# system.net
KiCad netlist of a schematic drawn in Altium Designer
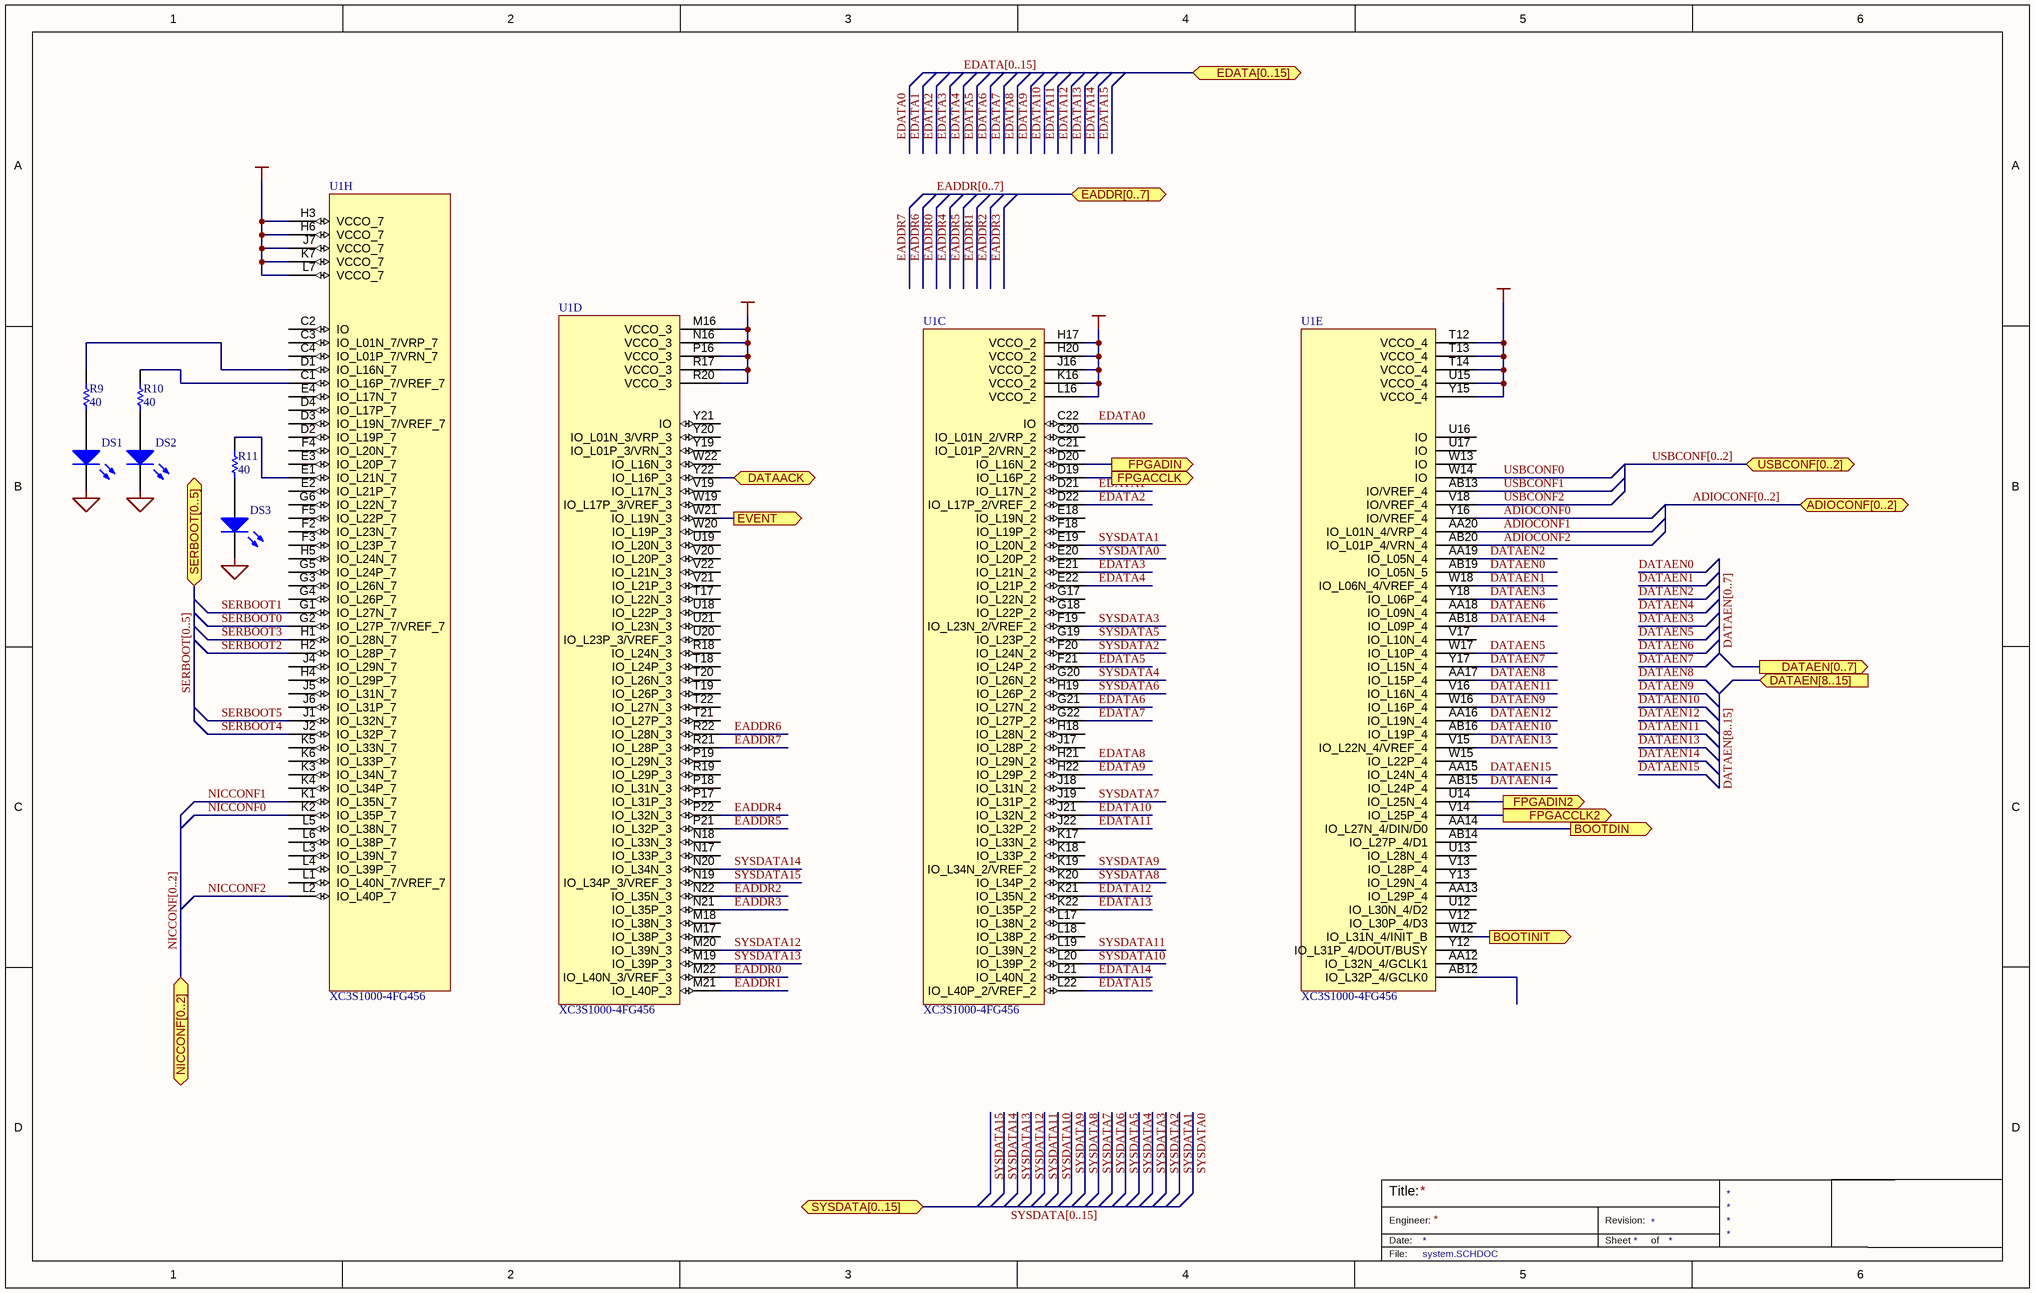
[diagram p0: system.SCHDOC]

(export (version "E")
  (design (tool "Eeschema 10.0.6"))
  (components
    (comp (ref "DS1")
      (value "LED0")
      (footprint "T-1_LED")
      (description "Typical INFRARED GaAs LED")
      (fields (field (name "MANUFACTURER") "Generic Components") (field (name "PUBLISHER") "Altium Limited"))
      (libsource (lib "Miscellaneous Devices") (part "LED0"))
    )
    (comp (ref "DS2")
      (value "LED0")
      (footprint "T-1_LED")
      (description "Typical INFRARED GaAs LED")
      (fields (field (name "MANUFACTURER") "Generic Components") (field (name "PUBLISHER") "Altium Limited"))
      (libsource (lib "Miscellaneous Devices") (part "LED0"))
    )
    (comp (ref "DS3")
      (value "LED0")
      (footprint "T-1_LED")
      (description "Typical INFRARED GaAs LED")
      (fields (field (name "MANUFACTURER") "Generic Components") (field (name "PUBLISHER") "Altium Limited"))
      (libsource (lib "Miscellaneous Devices") (part "LED0"))
    )
    (comp (ref "R9")
      (value "40")
      (footprint "CC1608-0603")
      (description "Resistor")
      (fields
        (field (name "MANUFACTURER") "Generic Components")
        (field (name "Comment") "Res1")
        (field (name "PUBLISHER") "Altium Limited")
      )
      (libsource (lib "Miscellaneous Devices") (part "Res1"))
    )
    (comp (ref "R10")
      (value "40")
      (footprint "CC1608-0603")
      (description "Resistor")
      (fields
        (field (name "MANUFACTURER") "Generic Components")
        (field (name "Comment") "Res1")
        (field (name "PUBLISHER") "Altium Limited")
      )
      (libsource (lib "Miscellaneous Devices") (part "Res1"))
    )
    (comp (ref "R11")
      (value "40")
      (footprint "CC1608-0603")
      (description "Resistor")
      (fields
        (field (name "MANUFACTURER") "Generic Components")
        (field (name "Comment") "Res1")
        (field (name "PUBLISHER") "Altium Limited")
      )
      (libsource (lib "Miscellaneous Devices") (part "Res1"))
    )
    (comp (ref "U1")
      (value "XC3S1000-4FG456")
      (footprint "FG456")
      (description "Xilinx Spartan-3 FPGA")
      (libsource (lib "parts") (part "XC3S1000-4FG456"))
    )
  )
  (nets
    (net (code "1") (name "/ADIOCONF0") (class "Default")
      (node (ref "U1") (pin "Y16") (pinfunction "IO/VREF_4_Y16") (pintype "power_in"))
    )
    (net (code "2") (name "/ADIOCONF1") (class "Default")
      (node (ref "U1") (pin "AA20") (pinfunction "IO_L01N_4/VRP_4_AA20") (pintype "power_in"))
    )
    (net (code "3") (name "/ADIOCONF2") (class "Default")
      (node (ref "U1") (pin "AB20") (pinfunction "IO_L01P_4/VRN_4_AB20") (pintype "power_in"))
    )
    (net (code "5") (name "/BOOTDIN") (class "Default")
      (node (ref "U1") (pin "AA14") (pinfunction "IO_L27N_4/DIN/D0_AA14") (pintype "power_in"))
    )
    (net (code "6") (name "/BOOTINIT") (class "Default")
      (node (ref "U1") (pin "W12") (pinfunction "IO_L31N_4/INIT_B_W12") (pintype "power_in"))
    )
    (net (code "7") (name "/DATAACK") (class "Default")
      (node (ref "U1") (pin "Y22") (pinfunction "IO_L16P_3_Y22") (pintype "bidirectional"))
    )
    (net (code "8") (name "/DATAEN0") (class "Default")
      (node (ref "U1") (pin "AB19") (pinfunction "IO_L05N_5_AB19") (pintype "power_in"))
    )
    (net (code "9") (name "/DATAEN1") (class "Default")
      (node (ref "U1") (pin "W18") (pinfunction "IO_L06N_4/VREF_4_W18") (pintype "power_in"))
    )
    (net (code "10") (name "/DATAEN2") (class "Default")
      (node (ref "U1") (pin "AA19") (pinfunction "IO_L05N_4_AA19") (pintype "power_in"))
    )
    (net (code "11") (name "/DATAEN3") (class "Default")
      (node (ref "U1") (pin "Y18") (pinfunction "IO_L06P_4_Y18") (pintype "power_in"))
    )
    (net (code "12") (name "/DATAEN4") (class "Default")
      (node (ref "U1") (pin "AB18") (pinfunction "IO_L09P_4_AB18") (pintype "power_in"))
    )
    (net (code "13") (name "/DATAEN5") (class "Default")
      (node (ref "U1") (pin "W17") (pinfunction "IO_L10P_4_W17") (pintype "power_in"))
    )
    (net (code "14") (name "/DATAEN6") (class "Default")
      (node (ref "U1") (pin "AA18") (pinfunction "IO_L09N_4_AA18") (pintype "power_in"))
    )
    (net (code "15") (name "/DATAEN7") (class "Default")
      (node (ref "U1") (pin "Y17") (pinfunction "IO_L15N_4_Y17") (pintype "power_in"))
    )
    (net (code "16") (name "/DATAEN8") (class "Default")
      (node (ref "U1") (pin "AA17") (pinfunction "IO_L15P_4_AA17") (pintype "power_in"))
    )
    (net (code "17") (name "/DATAEN9") (class "Default")
      (node (ref "U1") (pin "W16") (pinfunction "IO_L16P_4_W16") (pintype "power_in"))
    )
    (net (code "18") (name "/DATAEN10") (class "Default")
      (node (ref "U1") (pin "AB16") (pinfunction "IO_L19P_4_AB16") (pintype "power_in"))
    )
    (net (code "19") (name "/DATAEN11") (class "Default")
      (node (ref "U1") (pin "V16") (pinfunction "IO_L16N_4_V16") (pintype "power_in"))
    )
    (net (code "20") (name "/DATAEN12") (class "Default")
      (node (ref "U1") (pin "AA16") (pinfunction "IO_L19N_4_AA16") (pintype "power_in"))
    )
    (net (code "21") (name "/DATAEN13") (class "Default")
      (node (ref "U1") (pin "V15") (pinfunction "IO_L22N_4/VREF_4_V15") (pintype "power_in"))
    )
    (net (code "22") (name "/DATAEN14") (class "Default")
      (node (ref "U1") (pin "AB15") (pinfunction "IO_L24P_4_AB15") (pintype "power_in"))
    )
    (net (code "23") (name "/DATAEN15") (class "Default")
      (node (ref "U1") (pin "AA15") (pinfunction "IO_L24N_4_AA15") (pintype "power_in"))
    )
    (net (code "26") (name "/EADDR0") (class "Default")
      (node (ref "U1") (pin "M22") (pinfunction "IO_L40N_3/VREF_3_M22") (pintype "bidirectional"))
    )
    (net (code "27") (name "/EADDR1") (class "Default")
      (node (ref "U1") (pin "M21") (pinfunction "IO_L40P_3_M21") (pintype "bidirectional"))
    )
    (net (code "28") (name "/EADDR2") (class "Default")
      (node (ref "U1") (pin "N22") (pinfunction "IO_L35N_3_N22") (pintype "bidirectional"))
    )
    (net (code "29") (name "/EADDR3") (class "Default")
      (node (ref "U1") (pin "N21") (pinfunction "IO_L35P_3_N21") (pintype "bidirectional"))
    )
    (net (code "30") (name "/EADDR4") (class "Default")
      (node (ref "U1") (pin "P22") (pinfunction "IO_L32N_3_P22") (pintype "bidirectional"))
    )
    (net (code "31") (name "/EADDR5") (class "Default")
      (node (ref "U1") (pin "P21") (pinfunction "IO_L32P_3_P21") (pintype "bidirectional"))
    )
    (net (code "32") (name "/EADDR6") (class "Default")
      (node (ref "U1") (pin "R22") (pinfunction "IO_L28N_3_R22") (pintype "bidirectional"))
    )
    (net (code "33") (name "/EADDR7") (class "Default")
      (node (ref "U1") (pin "R21") (pinfunction "IO_L28P_3_R21") (pintype "bidirectional"))
    )
    (net (code "35") (name "/EDATA0") (class "Default")
      (node (ref "U1") (pin "C22") (pinfunction "IO_C22") (pintype "bidirectional"))
    )
    (net (code "36") (name "/EDATA1") (class "Default")
      (node (ref "U1") (pin "D21") (pinfunction "IO_L17N_2_D21") (pintype "bidirectional"))
    )
    (net (code "37") (name "/EDATA2") (class "Default")
      (node (ref "U1") (pin "D22") (pinfunction "IO_L17P_2/VREF_2_D22") (pintype "bidirectional"))
    )
    (net (code "38") (name "/EDATA3") (class "Default")
      (node (ref "U1") (pin "E21") (pinfunction "IO_L21N_2_E21") (pintype "bidirectional"))
    )
    (net (code "39") (name "/EDATA4") (class "Default")
      (node (ref "U1") (pin "E22") (pinfunction "IO_L21P_2_E22") (pintype "bidirectional"))
    )
    (net (code "40") (name "/EDATA5") (class "Default")
      (node (ref "U1") (pin "F21") (pinfunction "IO_L24P_2_F21") (pintype "bidirectional"))
    )
    (net (code "41") (name "/EDATA6") (class "Default")
      (node (ref "U1") (pin "G21") (pinfunction "IO_L27N_2_G21") (pintype "bidirectional"))
    )
    (net (code "42") (name "/EDATA7") (class "Default")
      (node (ref "U1") (pin "G22") (pinfunction "IO_L27P_2_G22") (pintype "bidirectional"))
    )
    (net (code "43") (name "/EDATA8") (class "Default")
      (node (ref "U1") (pin "H21") (pinfunction "IO_L29N_2_H21") (pintype "bidirectional"))
    )
    (net (code "44") (name "/EDATA9") (class "Default")
      (node (ref "U1") (pin "H22") (pinfunction "IO_L29P_2_H22") (pintype "bidirectional"))
    )
    (net (code "45") (name "/EDATA10") (class "Default")
      (node (ref "U1") (pin "J21") (pinfunction "IO_L32N_2_J21") (pintype "bidirectional"))
    )
    (net (code "46") (name "/EDATA11") (class "Default")
      (node (ref "U1") (pin "J22") (pinfunction "IO_L32P_2_J22") (pintype "bidirectional"))
    )
    (net (code "47") (name "/EDATA12") (class "Default")
      (node (ref "U1") (pin "K21") (pinfunction "IO_L35N_2_K21") (pintype "bidirectional"))
    )
    (net (code "48") (name "/EDATA13") (class "Default")
      (node (ref "U1") (pin "K22") (pinfunction "IO_L35P_2_K22") (pintype "bidirectional"))
    )
    (net (code "49") (name "/EDATA14") (class "Default")
      (node (ref "U1") (pin "L21") (pinfunction "IO_L40N_2_L21") (pintype "bidirectional"))
    )
    (net (code "50") (name "/EDATA15") (class "Default")
      (node (ref "U1") (pin "L22") (pinfunction "IO_L40P_2/VREF_2_L22") (pintype "bidirectional"))
    )
    (net (code "52") (name "/EVENT") (class "Default")
      (node (ref "U1") (pin "W21") (pinfunction "IO_L19N_3_W21") (pintype "bidirectional"))
    )
    (net (code "53") (name "/FPGACCLK") (class "Default")
      (node (ref "U1") (pin "D19") (pinfunction "IO_L16P_2_D19") (pintype "bidirectional"))
    )
    (net (code "54") (name "/FPGACCLK2") (class "Default")
      (node (ref "U1") (pin "V14") (pinfunction "IO_L25P_4_V14") (pintype "power_in"))
    )
    (net (code "55") (name "/FPGADIN") (class "Default")
      (node (ref "U1") (pin "D20") (pinfunction "IO_L16N_2_D20") (pintype "bidirectional"))
    )
    (net (code "56") (name "/FPGADIN2") (class "Default")
      (node (ref "U1") (pin "U14") (pinfunction "IO_L25N_4_U14") (pintype "power_in"))
    )
    (net (code "57") (name "/NICCONF0") (class "Default")
      (node (ref "U1") (pin "K2") (pinfunction "IO_L35P_7_K2") (pintype "bidirectional"))
    )
    (net (code "58") (name "/NICCONF1") (class "Default")
      (node (ref "U1") (pin "K1") (pinfunction "IO_L35N_7_K1") (pintype "bidirectional"))
    )
    (net (code "59") (name "/NICCONF2") (class "Default")
      (node (ref "U1") (pin "L2") (pinfunction "IO_L40P_7_L2") (pintype "bidirectional"))
    )
    (net (code "61") (name "/SERBOOT0") (class "Default")
      (node (ref "U1") (pin "G2") (pinfunction "IO_L27P_7/VREF_7_G2") (pintype "bidirectional"))
    )
    (net (code "62") (name "/SERBOOT1") (class "Default")
      (node (ref "U1") (pin "G1") (pinfunction "IO_L27N_7_G1") (pintype "bidirectional"))
    )
    (net (code "63") (name "/SERBOOT2") (class "Default")
      (node (ref "U1") (pin "H2") (pinfunction "IO_L28P_7_H2") (pintype "bidirectional"))
    )
    (net (code "64") (name "/SERBOOT3") (class "Default")
      (node (ref "U1") (pin "H1") (pinfunction "IO_L28N_7_H1") (pintype "bidirectional"))
    )
    (net (code "65") (name "/SERBOOT4") (class "Default")
      (node (ref "U1") (pin "J2") (pinfunction "IO_L32P_7_J2") (pintype "bidirectional"))
    )
    (net (code "66") (name "/SERBOOT5") (class "Default")
      (node (ref "U1") (pin "J1") (pinfunction "IO_L32N_7_J1") (pintype "bidirectional"))
    )
    (net (code "68") (name "/SYSDATA0") (class "Default")
      (node (ref "U1") (pin "E20") (pinfunction "IO_L20P_2_E20") (pintype "bidirectional"))
    )
    (net (code "69") (name "/SYSDATA1") (class "Default")
      (node (ref "U1") (pin "E19") (pinfunction "IO_L20N_2_E19") (pintype "bidirectional"))
    )
    (net (code "70") (name "/SYSDATA2") (class "Default")
      (node (ref "U1") (pin "F20") (pinfunction "IO_L24N_2_F20") (pintype "bidirectional"))
    )
    (net (code "71") (name "/SYSDATA3") (class "Default")
      (node (ref "U1") (pin "F19") (pinfunction "IO_L23N_2/VREF_2_F19") (pintype "bidirectional"))
    )
    (net (code "72") (name "/SYSDATA4") (class "Default")
      (node (ref "U1") (pin "G20") (pinfunction "IO_L26N_2_G20") (pintype "bidirectional"))
    )
    (net (code "73") (name "/SYSDATA5") (class "Default")
      (node (ref "U1") (pin "G19") (pinfunction "IO_L23P_2_G19") (pintype "bidirectional"))
    )
    (net (code "74") (name "/SYSDATA6") (class "Default")
      (node (ref "U1") (pin "H19") (pinfunction "IO_L26P_2_H19") (pintype "bidirectional"))
    )
    (net (code "75") (name "/SYSDATA7") (class "Default")
      (node (ref "U1") (pin "J19") (pinfunction "IO_L31P_2_J19") (pintype "bidirectional"))
    )
    (net (code "76") (name "/SYSDATA8") (class "Default")
      (node (ref "U1") (pin "K20") (pinfunction "IO_L34P_2_K20") (pintype "bidirectional"))
    )
    (net (code "77") (name "/SYSDATA9") (class "Default")
      (node (ref "U1") (pin "K19") (pinfunction "IO_L34N_2/VREF_2_K19") (pintype "bidirectional"))
    )
    (net (code "78") (name "/SYSDATA10") (class "Default")
      (node (ref "U1") (pin "L20") (pinfunction "IO_L39P_2_L20") (pintype "bidirectional"))
    )
    (net (code "79") (name "/SYSDATA11") (class "Default")
      (node (ref "U1") (pin "L19") (pinfunction "IO_L39N_2_L19") (pintype "bidirectional"))
    )
    (net (code "80") (name "/SYSDATA12") (class "Default")
      (node (ref "U1") (pin "M20") (pinfunction "IO_L39N_3_M20") (pintype "bidirectional"))
    )
    (net (code "81") (name "/SYSDATA13") (class "Default")
      (node (ref "U1") (pin "M19") (pinfunction "IO_L39P_3_M19") (pintype "bidirectional"))
    )
    (net (code "82") (name "/SYSDATA14") (class "Default")
      (node (ref "U1") (pin "N20") (pinfunction "IO_L34N_3_N20") (pintype "bidirectional"))
    )
    (net (code "83") (name "/SYSDATA15") (class "Default")
      (node (ref "U1") (pin "N19") (pinfunction "IO_L34P_3/VREF_3_N19") (pintype "bidirectional"))
    )
    (net (code "85") (name "/USBCONF0") (class "Default")
      (node (ref "U1") (pin "W14") (pinfunction "IO_W14") (pintype "power_in"))
    )
    (net (code "86") (name "/USBCONF1") (class "Default")
      (node (ref "U1") (pin "AB13") (pinfunction "IO/VREF_4_AB13") (pintype "power_in"))
    )
    (net (code "87") (name "/USBCONF2") (class "Default")
      (node (ref "U1") (pin "V18") (pinfunction "IO/VREF_4_V18") (pintype "power_in"))
    )
    (net (code "89") (name "GND") (class "Default")
      (node (ref "DS1") (pin "2") (pinfunction "K_2") (pintype "passive"))
      (node (ref "DS2") (pin "2") (pinfunction "K_2") (pintype "passive"))
      (node (ref "DS3") (pin "2") (pinfunction "K_2") (pintype "passive"))
    )
    (net (code "90") (name "Net-(DS1-A)") (class "Default")
      (node (ref "DS1") (pin "1") (pinfunction "A_1") (pintype "passive"))
      (node (ref "R9") (pin "1") (pinfunction "1_1") (pintype "passive"))
    )
    (net (code "91") (name "Net-(DS2-A)") (class "Default")
      (node (ref "DS2") (pin "1") (pinfunction "A_1") (pintype "passive"))
      (node (ref "R10") (pin "1") (pinfunction "1_1") (pintype "passive"))
    )
    (net (code "92") (name "Net-(DS3-A)") (class "Default")
      (node (ref "DS3") (pin "1") (pinfunction "A_1") (pintype "passive"))
      (node (ref "R11") (pin "1") (pinfunction "1_1") (pintype "passive"))
    )
    (net (code "93") (name "Net-(U1H-IO_L16N_7)") (class "Default")
      (node (ref "R9") (pin "2") (pinfunction "2_2") (pintype "passive"))
      (node (ref "U1") (pin "D1") (pinfunction "IO_L16N_7_D1") (pintype "bidirectional"))
    )
    (net (code "94") (name "Net-(U1H-IO_L16P_7{slash}VREF_7)") (class "Default")
      (node (ref "R10") (pin "2") (pinfunction "2_2") (pintype "passive"))
      (node (ref "U1") (pin "C1") (pinfunction "IO_L16P_7/VREF_7_C1") (pintype "bidirectional"))
    )
    (net (code "95") (name "Net-(U1H-IO_L21N_7)") (class "Default")
      (node (ref "R11") (pin "2") (pinfunction "2_2") (pintype "passive"))
      (node (ref "U1") (pin "E1") (pinfunction "IO_L21N_7_E1") (pintype "bidirectional"))
    )
    (net (code "96") (name "VCC") (class "Default")
      (node (ref "U1") (pin "H17") (pinfunction "VCCO_2_H17") (pintype "power_in"))
      (node (ref "U1") (pin "H20") (pinfunction "VCCO_2_H20") (pintype "power_in"))
      (node (ref "U1") (pin "H3") (pinfunction "VCCO_7_H3") (pintype "bidirectional"))
      (node (ref "U1") (pin "H6") (pinfunction "VCCO_7_H6") (pintype "bidirectional"))
      (node (ref "U1") (pin "J16") (pinfunction "VCCO_2_J16") (pintype "power_in"))
      (node (ref "U1") (pin "J7") (pinfunction "VCCO_7_J7") (pintype "bidirectional"))
      (node (ref "U1") (pin "K16") (pinfunction "VCCO_2_K16") (pintype "power_in"))
      (node (ref "U1") (pin "K7") (pinfunction "VCCO_7_K7") (pintype "bidirectional"))
      (node (ref "U1") (pin "L16") (pinfunction "VCCO_2_L16") (pintype "power_in"))
      (node (ref "U1") (pin "L7") (pinfunction "VCCO_7_L7") (pintype "bidirectional"))
      (node (ref "U1") (pin "M16") (pinfunction "VCCO_3_M16") (pintype "power_in"))
      (node (ref "U1") (pin "N16") (pinfunction "VCCO_3_N16") (pintype "power_in"))
      (node (ref "U1") (pin "P16") (pinfunction "VCCO_3_P16") (pintype "power_in"))
      (node (ref "U1") (pin "R17") (pinfunction "VCCO_3_R17") (pintype "power_in"))
      (node (ref "U1") (pin "R20") (pinfunction "VCCO_3_R20") (pintype "power_in"))
      (node (ref "U1") (pin "T12") (pinfunction "VCCO_4_T12") (pintype "power_in"))
      (node (ref "U1") (pin "T13") (pinfunction "VCCO_4_T13") (pintype "power_in"))
      (node (ref "U1") (pin "T14") (pinfunction "VCCO_4_T14") (pintype "power_in"))
      (node (ref "U1") (pin "U15") (pinfunction "VCCO_4_U15") (pintype "power_in"))
      (node (ref "U1") (pin "Y15") (pinfunction "VCCO_4_Y15") (pintype "power_in"))
    )
    (net (code "97") (name "unconnected-(U1C-IO_L01N_2{slash}VRP_2-PadC20)") (class "Default")
      (node (ref "U1") (pin "C20") (pinfunction "IO_L01N_2/VRP_2_C20") (pintype "bidirectional"))
    )
    (net (code "98") (name "unconnected-(U1C-IO_L01P_2{slash}VRN_2-PadC21)") (class "Default")
      (node (ref "U1") (pin "C21") (pinfunction "IO_L01P_2/VRN_2_C21") (pintype "bidirectional"))
    )
    (net (code "99") (name "unconnected-(U1C-IO_L19N_2-PadE18)") (class "Default")
      (node (ref "U1") (pin "E18") (pinfunction "IO_L19N_2_E18") (pintype "bidirectional"))
    )
    (net (code "100") (name "unconnected-(U1C-IO_L19P_2-PadF18)") (class "Default")
      (node (ref "U1") (pin "F18") (pinfunction "IO_L19P_2_F18") (pintype "bidirectional"))
    )
    (net (code "101") (name "unconnected-(U1C-IO_L22N_2-PadG17)") (class "Default")
      (node (ref "U1") (pin "G17") (pinfunction "IO_L22N_2_G17") (pintype "bidirectional"))
    )
    (net (code "102") (name "unconnected-(U1C-IO_L22P_2-PadG18)") (class "Default")
      (node (ref "U1") (pin "G18") (pinfunction "IO_L22P_2_G18") (pintype "bidirectional"))
    )
    (net (code "103") (name "unconnected-(U1C-IO_L28N_2-PadH18)") (class "Default")
      (node (ref "U1") (pin "H18") (pinfunction "IO_L28N_2_H18") (pintype "bidirectional"))
    )
    (net (code "104") (name "unconnected-(U1C-IO_L28P_2-PadJ17)") (class "Default")
      (node (ref "U1") (pin "J17") (pinfunction "IO_L28P_2_J17") (pintype "bidirectional"))
    )
    (net (code "105") (name "unconnected-(U1C-IO_L31N_2-PadJ18)") (class "Default")
      (node (ref "U1") (pin "J18") (pinfunction "IO_L31N_2_J18") (pintype "bidirectional"))
    )
    (net (code "106") (name "unconnected-(U1C-IO_L33N_2-PadK17)") (class "Default")
      (node (ref "U1") (pin "K17") (pinfunction "IO_L33N_2_K17") (pintype "bidirectional"))
    )
    (net (code "107") (name "unconnected-(U1C-IO_L33P_2-PadK18)") (class "Default")
      (node (ref "U1") (pin "K18") (pinfunction "IO_L33P_2_K18") (pintype "bidirectional"))
    )
    (net (code "108") (name "unconnected-(U1C-IO_L38N_2-PadL17)") (class "Default")
      (node (ref "U1") (pin "L17") (pinfunction "IO_L38N_2_L17") (pintype "bidirectional"))
    )
    (net (code "109") (name "unconnected-(U1C-IO_L38P_2-PadL18)") (class "Default")
      (node (ref "U1") (pin "L18") (pinfunction "IO_L38P_2_L18") (pintype "bidirectional"))
    )
    (net (code "110") (name "unconnected-(U1D-IO-PadY21)") (class "Default")
      (node (ref "U1") (pin "Y21") (pinfunction "IO_Y21") (pintype "bidirectional"))
    )
    (net (code "111") (name "unconnected-(U1D-IO_L01N_3{slash}VRP_3-PadY20)") (class "Default")
      (node (ref "U1") (pin "Y20") (pinfunction "IO_L01N_3/VRP_3_Y20") (pintype "bidirectional"))
    )
    (net (code "112") (name "unconnected-(U1D-IO_L01P_3{slash}VRN_3-PadY19)") (class "Default")
      (node (ref "U1") (pin "Y19") (pinfunction "IO_L01P_3/VRN_3_Y19") (pintype "bidirectional"))
    )
    (net (code "113") (name "unconnected-(U1D-IO_L16N_3-PadW22)") (class "Default")
      (node (ref "U1") (pin "W22") (pinfunction "IO_L16N_3_W22") (pintype "bidirectional"))
    )
    (net (code "114") (name "unconnected-(U1D-IO_L17N_3-PadV19)") (class "Default")
      (node (ref "U1") (pin "V19") (pinfunction "IO_L17N_3_V19") (pintype "bidirectional"))
    )
    (net (code "115") (name "unconnected-(U1D-IO_L17P_3{slash}VREF_3-PadW19)") (class "Default")
      (node (ref "U1") (pin "W19") (pinfunction "IO_L17P_3/VREF_3_W19") (pintype "bidirectional"))
    )
    (net (code "116") (name "unconnected-(U1D-IO_L19P_3-PadW20)") (class "Default")
      (node (ref "U1") (pin "W20") (pinfunction "IO_L19P_3_W20") (pintype "bidirectional"))
    )
    (net (code "117") (name "unconnected-(U1D-IO_L20N_3-PadU19)") (class "Default")
      (node (ref "U1") (pin "U19") (pinfunction "IO_L20N_3_U19") (pintype "bidirectional"))
    )
    (net (code "118") (name "unconnected-(U1D-IO_L20P_3-PadV20)") (class "Default")
      (node (ref "U1") (pin "V20") (pinfunction "IO_L20P_3_V20") (pintype "bidirectional"))
    )
    (net (code "119") (name "unconnected-(U1D-IO_L21N_3-PadV22)") (class "Default")
      (node (ref "U1") (pin "V22") (pinfunction "IO_L21N_3_V22") (pintype "bidirectional"))
    )
    (net (code "120") (name "unconnected-(U1D-IO_L21P_3-PadV21)") (class "Default")
      (node (ref "U1") (pin "V21") (pinfunction "IO_L21P_3_V21") (pintype "bidirectional"))
    )
    (net (code "121") (name "unconnected-(U1D-IO_L22N_3-PadT17)") (class "Default")
      (node (ref "U1") (pin "T17") (pinfunction "IO_L22N_3_T17") (pintype "bidirectional"))
    )
    (net (code "122") (name "unconnected-(U1D-IO_L22P_3-PadU18)") (class "Default")
      (node (ref "U1") (pin "U18") (pinfunction "IO_L22P_3_U18") (pintype "bidirectional"))
    )
    (net (code "123") (name "unconnected-(U1D-IO_L23N_3-PadU21)") (class "Default")
      (node (ref "U1") (pin "U21") (pinfunction "IO_L23N_3_U21") (pintype "bidirectional"))
    )
    (net (code "124") (name "unconnected-(U1D-IO_L23P_3{slash}VREF_3-PadU20)") (class "Default")
      (node (ref "U1") (pin "U20") (pinfunction "IO_L23P_3/VREF_3_U20") (pintype "bidirectional"))
    )
    (net (code "125") (name "unconnected-(U1D-IO_L24N_3-PadR18)") (class "Default")
      (node (ref "U1") (pin "R18") (pinfunction "IO_L24N_3_R18") (pintype "bidirectional"))
    )
    (net (code "126") (name "unconnected-(U1D-IO_L24P_3-PadT18)") (class "Default")
      (node (ref "U1") (pin "T18") (pinfunction "IO_L24P_3_T18") (pintype "bidirectional"))
    )
    (net (code "127") (name "unconnected-(U1D-IO_L26N_3-PadT20)") (class "Default")
      (node (ref "U1") (pin "T20") (pinfunction "IO_L26N_3_T20") (pintype "bidirectional"))
    )
    (net (code "128") (name "unconnected-(U1D-IO_L26P_3-PadT19)") (class "Default")
      (node (ref "U1") (pin "T19") (pinfunction "IO_L26P_3_T19") (pintype "bidirectional"))
    )
    (net (code "129") (name "unconnected-(U1D-IO_L27N_3-PadT22)") (class "Default")
      (node (ref "U1") (pin "T22") (pinfunction "IO_L27N_3_T22") (pintype "bidirectional"))
    )
    (net (code "130") (name "unconnected-(U1D-IO_L27P_3-PadT21)") (class "Default")
      (node (ref "U1") (pin "T21") (pinfunction "IO_L27P_3_T21") (pintype "bidirectional"))
    )
    (net (code "131") (name "unconnected-(U1D-IO_L29N_3-PadP19)") (class "Default")
      (node (ref "U1") (pin "P19") (pinfunction "IO_L29N_3_P19") (pintype "bidirectional"))
    )
    (net (code "132") (name "unconnected-(U1D-IO_L29P_3-PadR19)") (class "Default")
      (node (ref "U1") (pin "R19") (pinfunction "IO_L29P_3_R19") (pintype "bidirectional"))
    )
    (net (code "133") (name "unconnected-(U1D-IO_L31N_3-PadP18)") (class "Default")
      (node (ref "U1") (pin "P18") (pinfunction "IO_L31N_3_P18") (pintype "bidirectional"))
    )
    (net (code "134") (name "unconnected-(U1D-IO_L31P_3-PadP17)") (class "Default")
      (node (ref "U1") (pin "P17") (pinfunction "IO_L31P_3_P17") (pintype "bidirectional"))
    )
    (net (code "135") (name "unconnected-(U1D-IO_L33N_3-PadN18)") (class "Default")
      (node (ref "U1") (pin "N18") (pinfunction "IO_L33N_3_N18") (pintype "bidirectional"))
    )
    (net (code "136") (name "unconnected-(U1D-IO_L33P_3-PadN17)") (class "Default")
      (node (ref "U1") (pin "N17") (pinfunction "IO_L33P_3_N17") (pintype "bidirectional"))
    )
    (net (code "137") (name "unconnected-(U1D-IO_L38N_3-PadM18)") (class "Default")
      (node (ref "U1") (pin "M18") (pinfunction "IO_L38N_3_M18") (pintype "bidirectional"))
    )
    (net (code "138") (name "unconnected-(U1D-IO_L38P_3-PadM17)") (class "Default")
      (node (ref "U1") (pin "M17") (pinfunction "IO_L38P_3_M17") (pintype "bidirectional"))
    )
    (net (code "139") (name "unconnected-(U1E-IO-PadU16)") (class "Default")
      (node (ref "U1") (pin "U16") (pinfunction "IO_U16") (pintype "power_in"))
    )
    (net (code "140") (name "unconnected-(U1E-IO-PadU17)") (class "Default")
      (node (ref "U1") (pin "U17") (pinfunction "IO_U17") (pintype "power_in"))
    )
    (net (code "141") (name "unconnected-(U1E-IO-PadW13)") (class "Default")
      (node (ref "U1") (pin "W13") (pinfunction "IO_W13") (pintype "power_in"))
    )
    (net (code "142") (name "unconnected-(U1E-IO_L10N_4-PadV17)") (class "Default")
      (node (ref "U1") (pin "V17") (pinfunction "IO_L10N_4_V17") (pintype "power_in"))
    )
    (net (code "143") (name "unconnected-(U1E-IO_L22P_4-PadW15)") (class "Default")
      (node (ref "U1") (pin "W15") (pinfunction "IO_L22P_4_W15") (pintype "power_in"))
    )
    (net (code "144") (name "unconnected-(U1E-IO_L27P_4{slash}D1-PadAB14)") (class "Default")
      (node (ref "U1") (pin "AB14") (pinfunction "IO_L27P_4/D1_AB14") (pintype "power_in"))
    )
    (net (code "145") (name "unconnected-(U1E-IO_L28N_4-PadU13)") (class "Default")
      (node (ref "U1") (pin "U13") (pinfunction "IO_L28N_4_U13") (pintype "power_in"))
    )
    (net (code "146") (name "unconnected-(U1E-IO_L28P_4-PadV13)") (class "Default")
      (node (ref "U1") (pin "V13") (pinfunction "IO_L28P_4_V13") (pintype "power_in"))
    )
    (net (code "147") (name "unconnected-(U1E-IO_L29N_4-PadY13)") (class "Default")
      (node (ref "U1") (pin "Y13") (pinfunction "IO_L29N_4_Y13") (pintype "power_in"))
    )
    (net (code "148") (name "unconnected-(U1E-IO_L29P_4-PadAA13)") (class "Default")
      (node (ref "U1") (pin "AA13") (pinfunction "IO_L29P_4_AA13") (pintype "power_in"))
    )
    (net (code "149") (name "unconnected-(U1E-IO_L30N_4{slash}D2-PadU12)") (class "Default")
      (node (ref "U1") (pin "U12") (pinfunction "IO_L30N_4/D2_U12") (pintype "power_in"))
    )
    (net (code "150") (name "unconnected-(U1E-IO_L30P_4{slash}D3-PadV12)") (class "Default")
      (node (ref "U1") (pin "V12") (pinfunction "IO_L30P_4/D3_V12") (pintype "power_in"))
    )
    (net (code "151") (name "unconnected-(U1E-IO_L31P_4{slash}DOUT{slash}BUSY-PadY12)") (class "Default")
      (node (ref "U1") (pin "Y12") (pinfunction "IO_L31P_4/DOUT/BUSY_Y12") (pintype "power_in"))
    )
    (net (code "152") (name "unconnected-(U1E-IO_L32N_4{slash}GCLK1-PadAA12)") (class "Default")
      (node (ref "U1") (pin "AA12") (pinfunction "IO_L32N_4/GCLK1_AA12") (pintype "power_in"))
    )
    (net (code "153") (name "unconnected-(U1E-IO_L32P_4{slash}GCLK0-PadAB12)") (class "Default")
      (node (ref "U1") (pin "AB12") (pinfunction "IO_L32P_4/GCLK0_AB12") (pintype "power_in"))
    )
    (net (code "154") (name "unconnected-(U1H-IO-PadC2)") (class "Default")
      (node (ref "U1") (pin "C2") (pinfunction "IO_C2") (pintype "bidirectional"))
    )
    (net (code "155") (name "unconnected-(U1H-IO_L01N_7{slash}VRP_7-PadC3)") (class "Default")
      (node (ref "U1") (pin "C3") (pinfunction "IO_L01N_7/VRP_7_C3") (pintype "bidirectional"))
    )
    (net (code "156") (name "unconnected-(U1H-IO_L01P_7{slash}VRN_7-PadC4)") (class "Default")
      (node (ref "U1") (pin "C4") (pinfunction "IO_L01P_7/VRN_7_C4") (pintype "bidirectional"))
    )
    (net (code "157") (name "unconnected-(U1H-IO_L17N_7-PadE4)") (class "Default")
      (node (ref "U1") (pin "E4") (pinfunction "IO_L17N_7_E4") (pintype "bidirectional"))
    )
    (net (code "158") (name "unconnected-(U1H-IO_L17P_7-PadD4)") (class "Default")
      (node (ref "U1") (pin "D4") (pinfunction "IO_L17P_7_D4") (pintype "bidirectional"))
    )
    (net (code "159") (name "unconnected-(U1H-IO_L19N_7{slash}VREF_7-PadD3)") (class "Default")
      (node (ref "U1") (pin "D3") (pinfunction "IO_L19N_7/VREF_7_D3") (pintype "bidirectional"))
    )
    (net (code "160") (name "unconnected-(U1H-IO_L19P_7-PadD2)") (class "Default")
      (node (ref "U1") (pin "D2") (pinfunction "IO_L19P_7_D2") (pintype "bidirectional"))
    )
    (net (code "161") (name "unconnected-(U1H-IO_L20N_7-PadF4)") (class "Default")
      (node (ref "U1") (pin "F4") (pinfunction "IO_L20N_7_F4") (pintype "bidirectional"))
    )
    (net (code "162") (name "unconnected-(U1H-IO_L20P_7-PadE3)") (class "Default")
      (node (ref "U1") (pin "E3") (pinfunction "IO_L20P_7_E3") (pintype "bidirectional"))
    )
    (net (code "163") (name "unconnected-(U1H-IO_L21P_7-PadE2)") (class "Default")
      (node (ref "U1") (pin "E2") (pinfunction "IO_L21P_7_E2") (pintype "bidirectional"))
    )
    (net (code "164") (name "unconnected-(U1H-IO_L22N_7-PadG6)") (class "Default")
      (node (ref "U1") (pin "G6") (pinfunction "IO_L22N_7_G6") (pintype "bidirectional"))
    )
    (net (code "165") (name "unconnected-(U1H-IO_L22P_7-PadF5)") (class "Default")
      (node (ref "U1") (pin "F5") (pinfunction "IO_L22P_7_F5") (pintype "bidirectional"))
    )
    (net (code "166") (name "unconnected-(U1H-IO_L23N_7-PadF2)") (class "Default")
      (node (ref "U1") (pin "F2") (pinfunction "IO_L23N_7_F2") (pintype "bidirectional"))
    )
    (net (code "167") (name "unconnected-(U1H-IO_L23P_7-PadF3)") (class "Default")
      (node (ref "U1") (pin "F3") (pinfunction "IO_L23P_7_F3") (pintype "bidirectional"))
    )
    (net (code "168") (name "unconnected-(U1H-IO_L24N_7-PadH5)") (class "Default")
      (node (ref "U1") (pin "H5") (pinfunction "IO_L24N_7_H5") (pintype "bidirectional"))
    )
    (net (code "169") (name "unconnected-(U1H-IO_L24P_7-PadG5)") (class "Default")
      (node (ref "U1") (pin "G5") (pinfunction "IO_L24P_7_G5") (pintype "bidirectional"))
    )
    (net (code "170") (name "unconnected-(U1H-IO_L26N_7-PadG3)") (class "Default")
      (node (ref "U1") (pin "G3") (pinfunction "IO_L26N_7_G3") (pintype "bidirectional"))
    )
    (net (code "171") (name "unconnected-(U1H-IO_L26P_7-PadG4)") (class "Default")
      (node (ref "U1") (pin "G4") (pinfunction "IO_L26P_7_G4") (pintype "bidirectional"))
    )
    (net (code "172") (name "unconnected-(U1H-IO_L29N_7-PadJ4)") (class "Default")
      (node (ref "U1") (pin "J4") (pinfunction "IO_L29N_7_J4") (pintype "bidirectional"))
    )
    (net (code "173") (name "unconnected-(U1H-IO_L29P_7-PadH4)") (class "Default")
      (node (ref "U1") (pin "H4") (pinfunction "IO_L29P_7_H4") (pintype "bidirectional"))
    )
    (net (code "174") (name "unconnected-(U1H-IO_L31N_7-PadJ5)") (class "Default")
      (node (ref "U1") (pin "J5") (pinfunction "IO_L31N_7_J5") (pintype "bidirectional"))
    )
    (net (code "175") (name "unconnected-(U1H-IO_L31P_7-PadJ6)") (class "Default")
      (node (ref "U1") (pin "J6") (pinfunction "IO_L31P_7_J6") (pintype "bidirectional"))
    )
    (net (code "176") (name "unconnected-(U1H-IO_L33N_7-PadK5)") (class "Default")
      (node (ref "U1") (pin "K5") (pinfunction "IO_L33N_7_K5") (pintype "bidirectional"))
    )
    (net (code "177") (name "unconnected-(U1H-IO_L33P_7-PadK6)") (class "Default")
      (node (ref "U1") (pin "K6") (pinfunction "IO_L33P_7_K6") (pintype "bidirectional"))
    )
    (net (code "178") (name "unconnected-(U1H-IO_L34N_7-PadK3)") (class "Default")
      (node (ref "U1") (pin "K3") (pinfunction "IO_L34N_7_K3") (pintype "bidirectional"))
    )
    (net (code "179") (name "unconnected-(U1H-IO_L34P_7-PadK4)") (class "Default")
      (node (ref "U1") (pin "K4") (pinfunction "IO_L34P_7_K4") (pintype "bidirectional"))
    )
    (net (code "180") (name "unconnected-(U1H-IO_L38N_7-PadL5)") (class "Default")
      (node (ref "U1") (pin "L5") (pinfunction "IO_L38N_7_L5") (pintype "bidirectional"))
    )
    (net (code "181") (name "unconnected-(U1H-IO_L38P_7-PadL6)") (class "Default")
      (node (ref "U1") (pin "L6") (pinfunction "IO_L38P_7_L6") (pintype "bidirectional"))
    )
    (net (code "182") (name "unconnected-(U1H-IO_L39N_7-PadL3)") (class "Default")
      (node (ref "U1") (pin "L3") (pinfunction "IO_L39N_7_L3") (pintype "bidirectional"))
    )
    (net (code "183") (name "unconnected-(U1H-IO_L39P_7-PadL4)") (class "Default")
      (node (ref "U1") (pin "L4") (pinfunction "IO_L39P_7_L4") (pintype "bidirectional"))
    )
    (net (code "184") (name "unconnected-(U1H-IO_L40N_7{slash}VREF_7-PadL1)") (class "Default")
      (node (ref "U1") (pin "L1") (pinfunction "IO_L40N_7/VREF_7_L1") (pintype "bidirectional"))
    )
  )
)
